# hub22_microusb.net
KiCad netlist of a schematic drawn in EAGLE
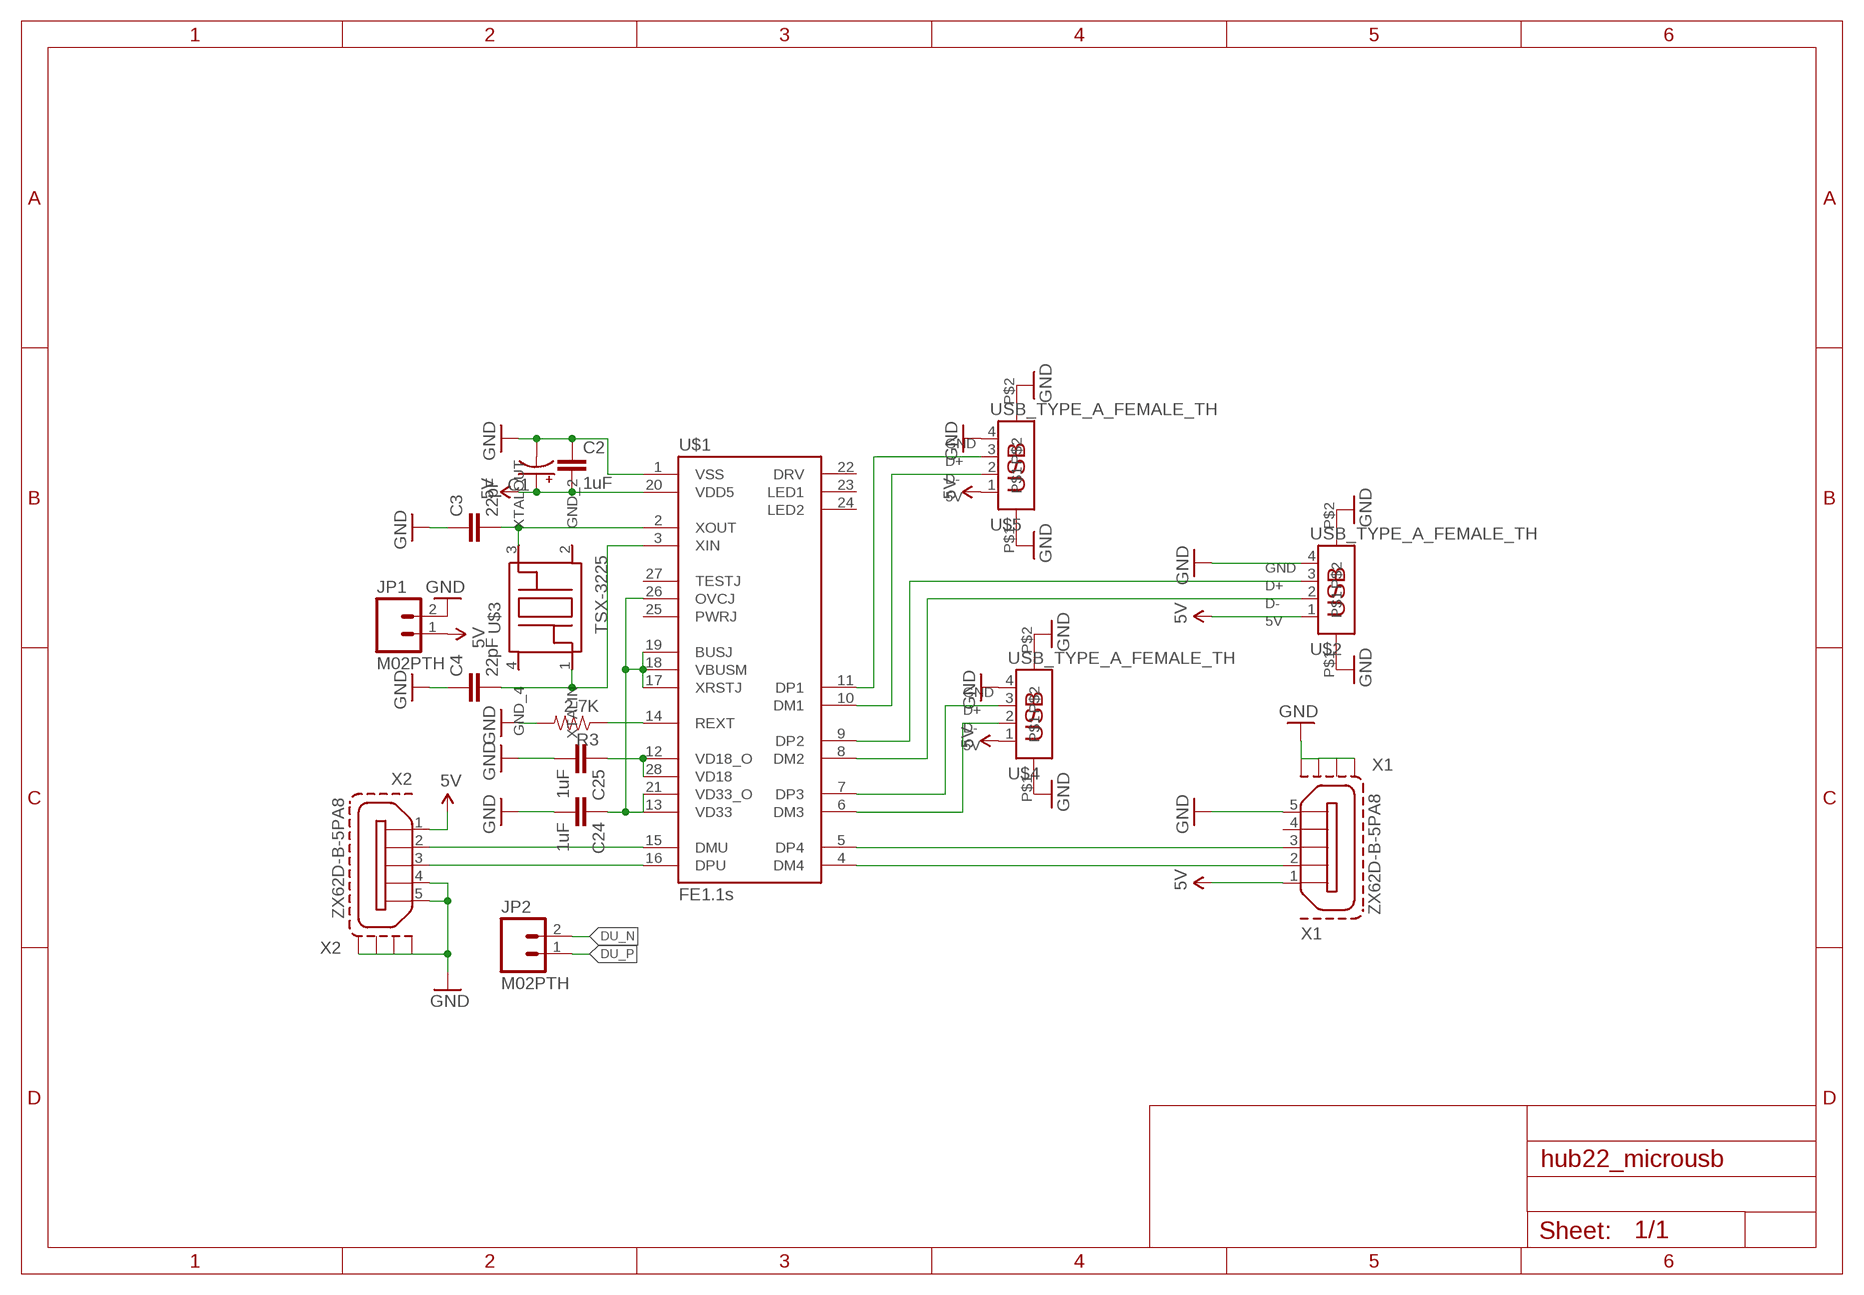
[diagram p0: schematic, sheet 1]

(export (version "E")
  (design (tool "Eeschema 10.0.6"))
  (components
    (comp (ref "C1")
      (value "CAP_POLD")
      (footprint "eagle-import:PANASONIC_D")
      (libsource (lib "eagle-import") (part "CAP_POLD"))
    )
    (comp (ref "C2")
      (value "1uF")
      (footprint "eagle-import:0805")
      (libsource (lib "eagle-import") (part "CAP0805"))
    )
    (comp (ref "C3")
      (value "22pF")
      (footprint "eagle-import:0805")
      (libsource (lib "eagle-import") (part "CAP0805"))
    )
    (comp (ref "C4")
      (value "22pF")
      (footprint "eagle-import:0805")
      (libsource (lib "eagle-import") (part "CAP0805"))
    )
    (comp (ref "C24")
      (value "1uF")
      (footprint "eagle-import:0805")
      (libsource (lib "eagle-import") (part "CAP0805"))
    )
    (comp (ref "C25")
      (value "1uF")
      (footprint "eagle-import:0805")
      (libsource (lib "eagle-import") (part "CAP0805"))
    )
    (comp (ref "JP1")
      (value "M02PTH")
      (footprint "eagle-import:1X02")
      (libsource (lib "eagle-import") (part "M02PTH"))
    )
    (comp (ref "JP2")
      (value "M02PTH")
      (footprint "eagle-import:1X02")
      (libsource (lib "eagle-import") (part "M02PTH"))
    )
    (comp (ref "R3")
      (value "2.7K")
      (footprint "eagle-import:0805")
      (libsource (lib "eagle-import") (part "RESISTOR0805-RES"))
    )
    (comp (ref "U$1")
      (value "FE1.1S")
      (footprint "eagle-import:FE1.1S_SSOP-28")
      (libsource (lib "eagle-import") (part "FE1.1S"))
    )
    (comp (ref "U$2")
      (value "USB_TYPE_A_FEMALE_TH")
      (footprint "eagle-import:USB_TYPE_A_FEMALE_TH")
      (libsource (lib "eagle-import") (part "USB_TYPE_A_FEMALE_TH"))
    )
    (comp (ref "U$3")
      (value "TSX-3225")
      (footprint "eagle-import:TSX-3225")
      (libsource (lib "eagle-import") (part "TSX-3225"))
    )
    (comp (ref "U$4")
      (value "USB_TYPE_A_FEMALE_TH")
      (footprint "eagle-import:USB_TYPE_A_FEMALE_TH")
      (libsource (lib "eagle-import") (part "USB_TYPE_A_FEMALE_TH"))
    )
    (comp (ref "U$5")
      (value "USB_TYPE_A_FEMALE_TH")
      (footprint "eagle-import:USB_TYPE_A_FEMALE_TH")
      (libsource (lib "eagle-import") (part "USB_TYPE_A_FEMALE_TH"))
    )
    (comp (ref "X1")
      (value "ZX62D-B-5PA8")
      (footprint "eagle-import:ZX62D-B-5PA8")
      (fields (field (name "MF") "Hirose"))
      (libsource (lib "eagle-import") (part "ZX62D-B-5PA8"))
    )
    (comp (ref "X2")
      (value "ZX62D-B-5PA8")
      (footprint "eagle-import:ZX62D-B-5PA8")
      (fields (field (name "MF") "Hirose"))
      (libsource (lib "eagle-import") (part "ZX62D-B-5PA8"))
    )
  )
  (nets
    (net (code "1") (name "5V") (class "Default")
      (node (ref "C1") (pin "+") (pinfunction "+_+") (pintype "passive"))
      (node (ref "C2") (pin "2") (pinfunction "2_2") (pintype "passive"))
      (node (ref "JP1") (pin "1") (pinfunction "1_1") (pintype "passive"))
      (node (ref "U$1") (pin "20") (pinfunction "VDD5_20") (pintype "bidirectional"))
      (node (ref "U$2") (pin "1") (pinfunction "1_1") (pintype "passive"))
      (node (ref "U$4") (pin "1") (pinfunction "1_1") (pintype "passive"))
      (node (ref "U$5") (pin "1") (pinfunction "1_1") (pintype "passive"))
      (node (ref "X1") (pin "1") (pinfunction "1_1") (pintype "passive"))
      (node (ref "X2") (pin "1") (pinfunction "1_1") (pintype "passive"))
    )
    (net (code "2") (name "DU_N") (class "Default")
      (node (ref "JP2") (pin "2") (pinfunction "2_2") (pintype "passive"))
      (node (ref "U$1") (pin "15") (pinfunction "DMU_15") (pintype "bidirectional"))
      (node (ref "X2") (pin "2") (pinfunction "2_2") (pintype "passive"))
    )
    (net (code "3") (name "DU_P") (class "Default")
      (node (ref "JP2") (pin "1") (pinfunction "1_1") (pintype "passive"))
      (node (ref "U$1") (pin "16") (pinfunction "DPU_16") (pintype "bidirectional"))
      (node (ref "X2") (pin "3") (pinfunction "3_3") (pintype "passive"))
    )
    (net (code "4") (name "GND") (class "Default")
      (node (ref "C1") (pin "-") (pinfunction "-_-") (pintype "passive"))
      (node (ref "C2") (pin "1") (pinfunction "1_1") (pintype "passive"))
      (node (ref "C24") (pin "2") (pinfunction "2_2") (pintype "passive"))
      (node (ref "C25") (pin "2") (pinfunction "2_2") (pintype "passive"))
      (node (ref "C3") (pin "1") (pinfunction "1_1") (pintype "passive"))
      (node (ref "C4") (pin "1") (pinfunction "1_1") (pintype "passive"))
      (node (ref "JP1") (pin "2") (pinfunction "2_2") (pintype "passive"))
      (node (ref "R3") (pin "2") (pinfunction "2_2") (pintype "passive"))
      (node (ref "U$1") (pin "1") (pinfunction "VSS_1") (pintype "bidirectional"))
      (node (ref "U$2") (pin "4") (pinfunction "4_4") (pintype "passive"))
      (node (ref "U$2") (pin "P$1") (pinfunction "P$1_P$1") (pintype "bidirectional"))
      (node (ref "U$2") (pin "P$2") (pinfunction "P$2_P$2") (pintype "bidirectional"))
      (node (ref "U$4") (pin "4") (pinfunction "4_4") (pintype "passive"))
      (node (ref "U$4") (pin "P$1") (pinfunction "P$1_P$1") (pintype "bidirectional"))
      (node (ref "U$4") (pin "P$2") (pinfunction "P$2_P$2") (pintype "bidirectional"))
      (node (ref "U$5") (pin "4") (pinfunction "4_4") (pintype "passive"))
      (node (ref "U$5") (pin "P$1") (pinfunction "P$1_P$1") (pintype "bidirectional"))
      (node (ref "U$5") (pin "P$2") (pinfunction "P$2_P$2") (pintype "bidirectional"))
      (node (ref "X1") (pin "5") (pinfunction "5_5") (pintype "passive"))
      (node (ref "X1") (pin "S1") (pinfunction "S1_S1") (pintype "passive"))
      (node (ref "X1") (pin "S2") (pinfunction "S2_S2") (pintype "passive"))
      (node (ref "X1") (pin "S3") (pinfunction "S3_S3") (pintype "passive"))
      (node (ref "X1") (pin "S4") (pinfunction "S4_S4") (pintype "passive"))
      (node (ref "X2") (pin "4") (pinfunction "4_4") (pintype "passive"))
      (node (ref "X2") (pin "5") (pinfunction "5_5") (pintype "passive"))
      (node (ref "X2") (pin "S1") (pinfunction "S1_S1") (pintype "passive"))
      (node (ref "X2") (pin "S2") (pinfunction "S2_S2") (pintype "passive"))
      (node (ref "X2") (pin "S3") (pinfunction "S3_S3") (pintype "passive"))
      (node (ref "X2") (pin "S4") (pinfunction "S4_S4") (pintype "passive"))
    )
    (net (code "5") (name "Net-(U$1-BUSJ)") (class "Default")
      (node (ref "C24") (pin "1") (pinfunction "1_1") (pintype "passive"))
      (node (ref "U$1") (pin "13") (pinfunction "VD33_13") (pintype "bidirectional"))
      (node (ref "U$1") (pin "17") (pinfunction "XRSTJ_17") (pintype "bidirectional"))
      (node (ref "U$1") (pin "18") (pinfunction "VBUSM_18") (pintype "bidirectional"))
      (node (ref "U$1") (pin "19") (pinfunction "BUSJ_19") (pintype "bidirectional"))
      (node (ref "U$1") (pin "21") (pinfunction "VD33_O_21") (pintype "bidirectional"))
      (node (ref "U$1") (pin "26") (pinfunction "OVCJ_26") (pintype "bidirectional"))
    )
    (net (code "6") (name "Net-(U$1-DM1)") (class "Default")
      (node (ref "U$1") (pin "10") (pinfunction "DM1_10") (pintype "bidirectional"))
      (node (ref "U$5") (pin "2") (pinfunction "2_2") (pintype "passive"))
    )
    (net (code "7") (name "Net-(U$1-DM2)") (class "Default")
      (node (ref "U$1") (pin "8") (pinfunction "DM2_8") (pintype "bidirectional"))
      (node (ref "U$2") (pin "2") (pinfunction "2_2") (pintype "passive"))
    )
    (net (code "8") (name "Net-(U$1-DM3)") (class "Default")
      (node (ref "U$1") (pin "6") (pinfunction "DM3_6") (pintype "bidirectional"))
      (node (ref "U$4") (pin "2") (pinfunction "2_2") (pintype "passive"))
    )
    (net (code "9") (name "Net-(U$1-DM4)") (class "Default")
      (node (ref "U$1") (pin "4") (pinfunction "DM4_4") (pintype "bidirectional"))
      (node (ref "X1") (pin "2") (pinfunction "2_2") (pintype "passive"))
    )
    (net (code "10") (name "Net-(U$1-DP1)") (class "Default")
      (node (ref "U$1") (pin "11") (pinfunction "DP1_11") (pintype "bidirectional"))
      (node (ref "U$5") (pin "3") (pinfunction "3_3") (pintype "passive"))
    )
    (net (code "11") (name "Net-(U$1-DP2)") (class "Default")
      (node (ref "U$1") (pin "9") (pinfunction "DP2_9") (pintype "bidirectional"))
      (node (ref "U$2") (pin "3") (pinfunction "3_3") (pintype "passive"))
    )
    (net (code "12") (name "Net-(U$1-DP3)") (class "Default")
      (node (ref "U$1") (pin "7") (pinfunction "DP3_7") (pintype "bidirectional"))
      (node (ref "U$4") (pin "3") (pinfunction "3_3") (pintype "passive"))
    )
    (net (code "13") (name "Net-(U$1-DP4)") (class "Default")
      (node (ref "U$1") (pin "5") (pinfunction "DP4_5") (pintype "bidirectional"))
      (node (ref "X1") (pin "3") (pinfunction "3_3") (pintype "passive"))
    )
    (net (code "14") (name "Net-(U$1-REXT)") (class "Default")
      (node (ref "R3") (pin "1") (pinfunction "1_1") (pintype "passive"))
      (node (ref "U$1") (pin "14") (pinfunction "REXT_14") (pintype "bidirectional"))
    )
    (net (code "15") (name "Net-(U$1-VD18)") (class "Default")
      (node (ref "C25") (pin "1") (pinfunction "1_1") (pintype "passive"))
      (node (ref "U$1") (pin "12") (pinfunction "VD18_O_12") (pintype "bidirectional"))
      (node (ref "U$1") (pin "28") (pinfunction "VD18_28") (pintype "bidirectional"))
    )
    (net (code "16") (name "Net-(U$1-XIN)") (class "Default")
      (node (ref "C4") (pin "2") (pinfunction "2_2") (pintype "passive"))
      (node (ref "U$1") (pin "3") (pinfunction "XIN_3") (pintype "bidirectional"))
      (node (ref "U$3") (pin "1") (pinfunction "XTALIN_1") (pintype "bidirectional"))
    )
    (net (code "17") (name "Net-(U$1-XOUT)") (class "Default")
      (node (ref "C3") (pin "2") (pinfunction "2_2") (pintype "passive"))
      (node (ref "U$1") (pin "2") (pinfunction "XOUT_2") (pintype "bidirectional"))
      (node (ref "U$3") (pin "3") (pinfunction "XTALOUT_3") (pintype "bidirectional"))
    )
    (net (code "18") (name "unconnected-(U$1-DRV-Pad22)") (class "Default")
      (node (ref "U$1") (pin "22") (pinfunction "DRV_22") (pintype "bidirectional"))
    )
    (net (code "19") (name "unconnected-(U$1-LED1-Pad23)") (class "Default")
      (node (ref "U$1") (pin "23") (pinfunction "LED1_23") (pintype "bidirectional"))
    )
    (net (code "20") (name "unconnected-(U$1-LED2-Pad24)") (class "Default")
      (node (ref "U$1") (pin "24") (pinfunction "LED2_24") (pintype "bidirectional"))
    )
    (net (code "21") (name "unconnected-(U$1-PWRJ-Pad25)") (class "Default")
      (node (ref "U$1") (pin "25") (pinfunction "PWRJ_25") (pintype "bidirectional"))
    )
    (net (code "22") (name "unconnected-(U$1-TESTJ-Pad27)") (class "Default")
      (node (ref "U$1") (pin "27") (pinfunction "TESTJ_27") (pintype "bidirectional"))
    )
    (net (code "23") (name "unconnected-(U$3-GND_2-Pad2)") (class "Default")
      (node (ref "U$3") (pin "2") (pinfunction "GND_2_2") (pintype "bidirectional"))
    )
    (net (code "24") (name "unconnected-(U$3-GND_4-Pad4)") (class "Default")
      (node (ref "U$3") (pin "4") (pinfunction "GND_4_4") (pintype "bidirectional"))
    )
    (net (code "25") (name "unconnected-(X1-Pad4)") (class "Default")
      (node (ref "X1") (pin "4") (pinfunction "4_4") (pintype "passive"))
    )
  )
)
